# buck.net
KiCad netlist of a schematic drawn in Altium Designer
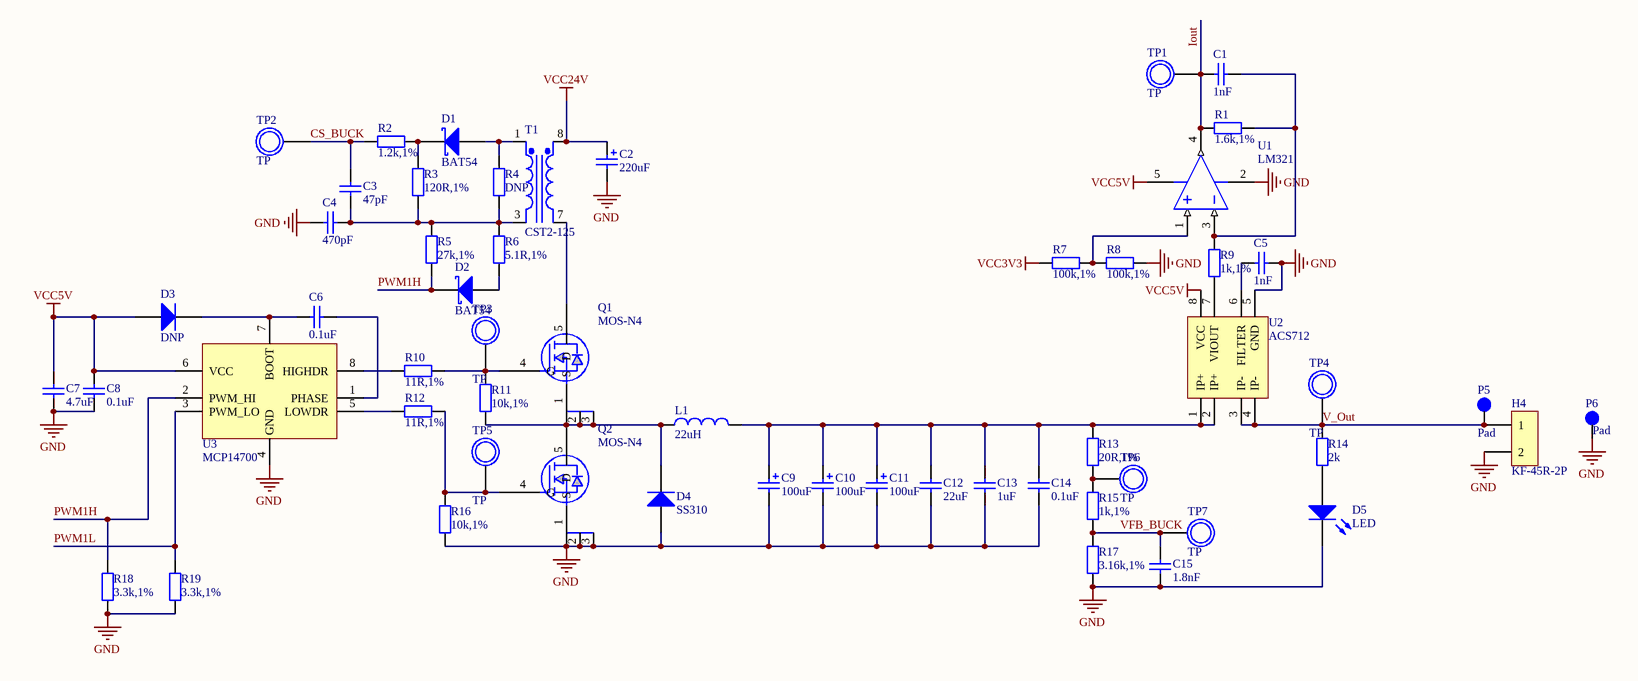
[diagram p0: buck.SchDoc]

(export (version "E")
  (design (tool "Eeschema 10.0.6"))
  (components
    (comp (ref "C1")
      (value "1nF")
      (footprint "CAP0603")
      (description "CAP NON-POL")
      (fields (field (name "TOLERANCE") "+/-10%"))
      (libsource (lib "Seer_Discrete") (part "CAP"))
    )
    (comp (ref "C2")
      (value "220uF")
      (footprint "CAPAE109103X105N")
      (description "cap pol")
      (fields (field (name "TOLERANCE") "~{+}- 10%"))
      (libsource (lib "Seer_Discrete") (part "CAP_Pol"))
    )
    (comp (ref "C3")
      (value "47pF")
      (footprint "CAP0603")
      (description "CAP NON-POL")
      (fields (field (name "TOLERANCE") "+/-10%"))
      (libsource (lib "Seer_Discrete") (part "CAP"))
    )
    (comp (ref "C4")
      (value "470pF")
      (footprint "CAP0603")
      (description "CAP NON-POL")
      (fields (field (name "TOLERANCE") "+/-10%"))
      (libsource (lib "Seer_Discrete") (part "CAP"))
    )
    (comp (ref "C5")
      (value "1nF")
      (footprint "CAP0603")
      (description "CAP NON-POL")
      (fields (field (name "TOLERANCE") "+/-10%"))
      (libsource (lib "Seer_Discrete") (part "CAP"))
    )
    (comp (ref "C6")
      (value "0.1uF")
      (footprint "CAP0603")
      (description "CAP NON-POL")
      (fields (field (name "TOLERANCE") "+/-10%"))
      (libsource (lib "Seer_Discrete") (part "CAP"))
    )
    (comp (ref "C7")
      (value "4.7uF")
      (footprint "CAP0603")
      (description "CAP NON-POL")
      (fields (field (name "TOLERANCE") "+/-10%"))
      (libsource (lib "Seer_Discrete") (part "CAP"))
    )
    (comp (ref "C8")
      (value "0.1uF")
      (footprint "CAP0603")
      (description "CAP NON-POL")
      (fields (field (name "TOLERANCE") "+/-10%"))
      (libsource (lib "Seer_Discrete") (part "CAP"))
    )
    (comp (ref "C9")
      (value "100uF")
      (footprint "CAPAE8983X105N")
      (description "cap pol")
      (fields (field (name "TOLERANCE") "~{+}- 10%"))
      (libsource (lib "Seer_Discrete") (part "CAP_Pol"))
    )
    (comp (ref "C10")
      (value "100uF")
      (footprint "CAPAE8983X105N")
      (description "cap pol")
      (fields (field (name "TOLERANCE") "~{+}- 10%"))
      (libsource (lib "Seer_Discrete") (part "CAP_Pol"))
    )
    (comp (ref "C11")
      (value "100uF")
      (footprint "CAPAE8983X105N")
      (description "cap pol")
      (fields (field (name "TOLERANCE") "~{+}- 10%"))
      (libsource (lib "Seer_Discrete") (part "CAP_Pol"))
    )
    (comp (ref "C12")
      (value "22uF")
      (footprint "CAP1206")
      (description "CAP NON-POL")
      (fields (field (name "TOLERANCE") "+/-10%"))
      (libsource (lib "Seer_Discrete") (part "CAP"))
    )
    (comp (ref "C13")
      (value "1uF")
      (footprint "CAP1206")
      (description "CAP NON-POL")
      (fields (field (name "TOLERANCE") "+/-10%"))
      (libsource (lib "Seer_Discrete") (part "CAP"))
    )
    (comp (ref "C14")
      (value "0.1uF")
      (footprint "CAP1206")
      (description "CAP NON-POL")
      (fields (field (name "TOLERANCE") "+/-10%"))
      (libsource (lib "Seer_Discrete") (part "CAP"))
    )
    (comp (ref "C15")
      (value "1.8nF")
      (footprint "CAP0603")
      (description "CAP NON-POL")
      (fields (field (name "TOLERANCE") "+/-10%"))
      (libsource (lib "Seer_Discrete") (part "CAP"))
    )
    (comp (ref "D1")
      (value "BAT54")
      (footprint "SOD250X100-2N")
      (description "Schottky Diode")
      (libsource (lib "Seer_Discrete") (part "Diode Schottky"))
    )
    (comp (ref "D2")
      (value "BAT54")
      (footprint "SOD250X100-2N")
      (description "Schottky Diode")
      (libsource (lib "Seer_Discrete") (part "Diode Schottky"))
    )
    (comp (ref "D3")
      (value "DNP")
      (footprint "SMA")
      (description "diode")
      (libsource (lib "Seer_Discrete") (part "Diode"))
    )
    (comp (ref "D4")
      (value "SS310")
      (footprint "SMA")
      (description "diode")
      (libsource (lib "Seer_Discrete") (part "Diode"))
    )
    (comp (ref "D5")
      (value "LED")
      (footprint "LED0402")
      (description "led")
      (libsource (lib "Seer_Discrete") (part "LED"))
    )
    (comp (ref "H4")
      (value "KF-45R-2P")
      (footprint "KF-45R-2P")
      (libsource (lib "Seer_XIAL") (part "KF-45R-2P"))
    )
    (comp (ref "L1")
      (value "22uH")
      (footprint "CDRH125")
      (description "Inductor")
      (libsource (lib "Seer_Discrete") (part "Inductor"))
    )
    (comp (ref "P5")
      (value "Pad")
      (footprint "PAD10x50")
      (description "PAD")
      (libsource (lib "Seer_XIAL") (part "Pad"))
    )
    (comp (ref "P6")
      (value "Pad")
      (footprint "PAD10x50")
      (description "PAD")
      (libsource (lib "Seer_XIAL") (part "Pad"))
    )
    (comp (ref "Q1")
      (value "MOS-N4")
      (footprint "QFN5x6")
      (description "N Channel MOSFET")
      (libsource (lib "Seer_Discrete") (part "MOS-N4"))
    )
    (comp (ref "Q2")
      (value "MOS-N4")
      (footprint "QFN5x6")
      (description "N Channel MOSFET")
      (libsource (lib "Seer_Discrete") (part "MOS-N4"))
    )
    (comp (ref "R1")
      (value "1.6k,1%")
      (footprint "RES0603")
      (description "res")
      (libsource (lib "") (part "RES_1"))
    )
    (comp (ref "R2")
      (value "1.2k,1%")
      (footprint "RES0603")
      (description "res")
      (libsource (lib "Seer_Discrete") (part "RES"))
    )
    (comp (ref "R3")
      (value "120R,1%")
      (footprint "RES0603")
      (description "res")
      (libsource (lib "") (part "RES_2"))
    )
    (comp (ref "R4")
      (value "DNP")
      (footprint "RES0603")
      (description "res")
      (libsource (lib "") (part "RES_3"))
    )
    (comp (ref "R5")
      (value "27k,1%")
      (footprint "RES0603")
      (description "res")
      (libsource (lib "") (part "RES_2"))
    )
    (comp (ref "R6")
      (value "5.1R,1%")
      (footprint "RES0603")
      (description "res")
      (libsource (lib "") (part "RES_2"))
    )
    (comp (ref "R7")
      (value "100k,1%")
      (footprint "RES0603")
      (description "res")
      (libsource (lib "Seer_Discrete") (part "RES"))
    )
    (comp (ref "R8")
      (value "100k,1%")
      (footprint "RES0603")
      (description "res")
      (libsource (lib "Seer_Discrete") (part "RES"))
    )
    (comp (ref "R9")
      (value "1k,1%")
      (footprint "RES0603")
      (description "res")
      (libsource (lib "") (part "RES_2"))
    )
    (comp (ref "R10")
      (value "11R,1%")
      (footprint "RES0603")
      (description "res")
      (libsource (lib "Seer_Discrete") (part "RES"))
    )
    (comp (ref "R11")
      (value "10k,1%")
      (footprint "RES0603")
      (description "res")
      (libsource (lib "") (part "RES_2"))
    )
    (comp (ref "R12")
      (value "11R,1%")
      (footprint "RES0603")
      (description "res")
      (libsource (lib "Seer_Discrete") (part "RES"))
    )
    (comp (ref "R13")
      (value "20R,1%")
      (footprint "RES0603")
      (description "res")
      (libsource (lib "") (part "RES_2"))
    )
    (comp (ref "R14")
      (value "2k")
      (footprint "RES0402")
      (description "res")
      (libsource (lib "") (part "RES_3"))
    )
    (comp (ref "R15")
      (value "1k,1%")
      (footprint "RES0603")
      (description "res")
      (libsource (lib "") (part "RES_2"))
    )
    (comp (ref "R16")
      (value "10k,1%")
      (footprint "RES0603")
      (description "res")
      (libsource (lib "") (part "RES_2"))
    )
    (comp (ref "R17")
      (value "3.16k,1%")
      (footprint "RES0603")
      (description "res")
      (libsource (lib "") (part "RES_2"))
    )
    (comp (ref "R18")
      (value "3.3k,1%")
      (footprint "RES0603")
      (description "res")
      (libsource (lib "") (part "RES_3"))
    )
    (comp (ref "R19")
      (value "3.3k,1%")
      (footprint "RES0603")
      (description "res")
      (libsource (lib "") (part "RES_3"))
    )
    (comp (ref "T1")
      (value "CST2-125")
      (footprint "CST2-125")
      (description "Current Transformer 1:125")
      (libsource (lib "Seer_IC") (part "CST2-125"))
    )
    (comp (ref "TP1")
      (value "TP")
      (footprint "PAD85R")
      (description "test point")
      (libsource (lib "Seer_XIAL") (part "Test_Point"))
    )
    (comp (ref "TP2")
      (value "TP")
      (footprint "PAD85R")
      (description "test point")
      (libsource (lib "Seer_XIAL") (part "Test_Point"))
    )
    (comp (ref "TP3")
      (value "TP")
      (footprint "PAD85R")
      (description "test point")
      (libsource (lib "Seer_XIAL") (part "Test_Point"))
    )
    (comp (ref "TP4")
      (value "TP")
      (footprint "PAD85R")
      (description "test point")
      (libsource (lib "Seer_XIAL") (part "Test_Point"))
    )
    (comp (ref "TP5")
      (value "TP")
      (footprint "PAD85R")
      (description "test point")
      (libsource (lib "Seer_XIAL") (part "Test_Point"))
    )
    (comp (ref "TP6")
      (value "TP")
      (footprint "PAD85R")
      (description "test point")
      (libsource (lib "Seer_XIAL") (part "Test_Point"))
    )
    (comp (ref "TP7")
      (value "TP")
      (footprint "PAD85R")
      (description "test point")
      (libsource (lib "Seer_XIAL") (part "Test_Point"))
    )
    (comp (ref "U1")
      (value "LM321")
      (footprint "SOT65P210X110-5N")
      (description "Low Power Single Op Amp")
      (libsource (lib "Seer_IC") (part "LM321"))
    )
    (comp (ref "U2")
      (value "ACS712")
      (footprint "SOP127P600X175-8N")
      (libsource (lib "Seer_IC") (part "ACS712"))
    )
    (comp (ref "U3")
      (value "MCP14700")
      (footprint "SOP127P600X175-8N")
      (description "Dual Input Synchronous MOSFET Driver")
      (libsource (lib "Seer_IC") (part "MCP14700"))
    )
  )
  (nets
    (net (code "1") (name "/CS_BUCK") (class "Default")
      (node (ref "C3") (pin "2") (pinfunction "2_2") (pintype "passive"))
      (node (ref "R2") (pin "2") (pinfunction "2_2") (pintype "passive"))
      (node (ref "TP2") (pin "1") (pinfunction "1_1") (pintype "passive"))
    )
    (net (code "2") (name "/Iout") (class "Default")
      (node (ref "C1") (pin "2") (pinfunction "2_2") (pintype "passive"))
      (node (ref "R1") (pin "1") (pinfunction "1_1") (pintype "passive"))
      (node (ref "TP1") (pin "1") (pinfunction "1_1") (pintype "passive"))
      (node (ref "U1") (pin "4") (pinfunction "OUT_4") (pintype "output"))
    )
    (net (code "3") (name "/PWM1H") (class "Default")
      (node (ref "D2") (pin "1") (pinfunction "K_1") (pintype "passive"))
      (node (ref "R18") (pin "2") (pinfunction "2_2") (pintype "passive"))
      (node (ref "R5") (pin "2") (pinfunction "2_2") (pintype "passive"))
      (node (ref "U3") (pin "2") (pinfunction "PWM_HI_2") (pintype "passive"))
    )
    (net (code "4") (name "/PWM1L") (class "Default")
      (node (ref "R19") (pin "2") (pinfunction "2_2") (pintype "passive"))
      (node (ref "U3") (pin "3") (pinfunction "PWM_LO_3") (pintype "passive"))
    )
    (net (code "5") (name "/VFB_BUCK") (class "Default")
      (node (ref "C15") (pin "2") (pinfunction "2_2") (pintype "passive"))
      (node (ref "R15") (pin "2") (pinfunction "2_2") (pintype "passive"))
      (node (ref "R17") (pin "1") (pinfunction "1_1") (pintype "passive"))
      (node (ref "TP7") (pin "1") (pinfunction "1_1") (pintype "passive"))
    )
    (net (code "6") (name "/V_Out") (class "Default")
      (node (ref "H4") (pin "1") (pinfunction "1_1") (pintype "passive"))
      (node (ref "P5") (pin "1") (pinfunction "1_1") (pintype "passive"))
      (node (ref "R14") (pin "2") (pinfunction "2_2") (pintype "passive"))
      (node (ref "TP4") (pin "1") (pinfunction "1_1") (pintype "passive"))
      (node (ref "U2") (pin "3") (pinfunction "IP-_3") (pintype "passive"))
      (node (ref "U2") (pin "4") (pinfunction "IP-_4") (pintype "passive"))
    )
    (net (code "7") (name "GND") (class "Default")
      (node (ref "C10") (pin "1") (pinfunction "1_1") (pintype "passive"))
      (node (ref "C11") (pin "1") (pinfunction "1_1") (pintype "passive"))
      (node (ref "C12") (pin "1") (pinfunction "1_1") (pintype "passive"))
      (node (ref "C13") (pin "1") (pinfunction "1_1") (pintype "passive"))
      (node (ref "C14") (pin "1") (pinfunction "1_1") (pintype "passive"))
      (node (ref "C15") (pin "1") (pinfunction "1_1") (pintype "passive"))
      (node (ref "C2") (pin "1") (pinfunction "1_1") (pintype "passive"))
      (node (ref "C4") (pin "2") (pinfunction "2_2") (pintype "passive"))
      (node (ref "C5") (pin "1") (pinfunction "1_1") (pintype "passive"))
      (node (ref "C7") (pin "1") (pinfunction "1_1") (pintype "passive"))
      (node (ref "C8") (pin "1") (pinfunction "1_1") (pintype "passive"))
      (node (ref "C9") (pin "1") (pinfunction "1_1") (pintype "passive"))
      (node (ref "D4") (pin "1") (pinfunction "A_1") (pintype "passive"))
      (node (ref "D5") (pin "2") (pinfunction "K_2") (pintype "passive"))
      (node (ref "H4") (pin "2") (pinfunction "2_2") (pintype "passive"))
      (node (ref "P6") (pin "1") (pinfunction "1_1") (pintype "passive"))
      (node (ref "Q2") (pin "1") (pinfunction "S_1") (pintype "passive"))
      (node (ref "Q2") (pin "2") (pintype "passive"))
      (node (ref "Q2") (pin "3") (pintype "passive"))
      (node (ref "R16") (pin "2") (pinfunction "2_2") (pintype "passive"))
      (node (ref "R17") (pin "2") (pinfunction "2_2") (pintype "passive"))
      (node (ref "R18") (pin "1") (pinfunction "1_1") (pintype "passive"))
      (node (ref "R19") (pin "1") (pinfunction "1_1") (pintype "passive"))
      (node (ref "R8") (pin "1") (pinfunction "1_1") (pintype "passive"))
      (node (ref "U1") (pin "2") (pinfunction "V-_2") (pintype "power_in"))
      (node (ref "U2") (pin "5") (pinfunction "GND_5") (pintype "passive"))
      (node (ref "U3") (pin "4") (pinfunction "GND_4") (pintype "passive"))
    )
    (net (code "8") (name "Net-(C10-Pad2)") (class "Default")
      (node (ref "C10") (pin "2") (pinfunction "2_2") (pintype "passive"))
      (node (ref "C11") (pin "2") (pinfunction "2_2") (pintype "passive"))
      (node (ref "C12") (pin "2") (pinfunction "2_2") (pintype "passive"))
      (node (ref "C13") (pin "2") (pinfunction "2_2") (pintype "passive"))
      (node (ref "C14") (pin "2") (pinfunction "2_2") (pintype "passive"))
      (node (ref "C9") (pin "2") (pinfunction "2_2") (pintype "passive"))
      (node (ref "L1") (pin "2") (pinfunction "2_2") (pintype "passive"))
      (node (ref "R13") (pin "1") (pinfunction "1_1") (pintype "passive"))
      (node (ref "U2") (pin "1") (pinfunction "IP+_1") (pintype "passive"))
      (node (ref "U2") (pin "2") (pinfunction "IP+_2") (pintype "passive"))
    )
    (net (code "9") (name "Net-(D1-A)") (class "Default")
      (node (ref "D1") (pin "2") (pinfunction "A_2") (pintype "passive"))
      (node (ref "R4") (pin "2") (pinfunction "2_2") (pintype "passive"))
      (node (ref "T1") (pin "1") (pinfunction "Sec+_1") (pintype "passive"))
    )
    (net (code "10") (name "Net-(D1-K)") (class "Default")
      (node (ref "D1") (pin "1") (pinfunction "K_1") (pintype "passive"))
      (node (ref "R2") (pin "1") (pinfunction "1_1") (pintype "passive"))
      (node (ref "R3") (pin "1") (pinfunction "1_1") (pintype "passive"))
    )
    (net (code "11") (name "Net-(D2-A)") (class "Default")
      (node (ref "D2") (pin "2") (pinfunction "A_2") (pintype "passive"))
      (node (ref "R6") (pin "2") (pinfunction "2_2") (pintype "passive"))
    )
    (net (code "12") (name "Net-(D3-K)") (class "Default")
      (node (ref "C6") (pin "2") (pinfunction "2_2") (pintype "passive"))
      (node (ref "D3") (pin "2") (pinfunction "K_2") (pintype "passive"))
      (node (ref "U3") (pin "7") (pinfunction "BOOT_7") (pintype "passive"))
    )
    (net (code "13") (name "Net-(D4-K)") (class "Default")
      (node (ref "D4") (pin "2") (pinfunction "K_2") (pintype "passive"))
      (node (ref "L1") (pin "1") (pinfunction "1_1") (pintype "passive"))
      (node (ref "Q1") (pin "1") (pinfunction "S_1") (pintype "passive"))
      (node (ref "Q1") (pin "2") (pintype "passive"))
      (node (ref "Q1") (pin "3") (pintype "passive"))
      (node (ref "Q2") (pin "5") (pinfunction "D_5") (pintype "passive"))
      (node (ref "R11") (pin "2") (pinfunction "2_2") (pintype "passive"))
    )
    (net (code "14") (name "Net-(D5-A)") (class "Default")
      (node (ref "D5") (pin "1") (pinfunction "A_1") (pintype "passive"))
      (node (ref "R14") (pin "1") (pinfunction "1_1") (pintype "passive"))
    )
    (net (code "15") (name "Net-(Q1-D)") (class "Default")
      (node (ref "Q1") (pin "5") (pinfunction "D_5") (pintype "passive"))
      (node (ref "T1") (pin "7") (pinfunction "Pri-_7") (pintype "passive"))
    )
    (net (code "16") (name "Net-(Q1-G)") (class "Default")
      (node (ref "Q1") (pin "4") (pinfunction "G_4") (pintype "passive"))
      (node (ref "R10") (pin "1") (pinfunction "1_1") (pintype "passive"))
      (node (ref "R11") (pin "1") (pinfunction "1_1") (pintype "passive"))
      (node (ref "TP3") (pin "1") (pinfunction "1_1") (pintype "passive"))
    )
    (net (code "17") (name "Net-(Q2-G)") (class "Default")
      (node (ref "Q2") (pin "4") (pinfunction "G_4") (pintype "passive"))
      (node (ref "R12") (pin "1") (pinfunction "1_1") (pintype "passive"))
      (node (ref "R16") (pin "1") (pinfunction "1_1") (pintype "passive"))
      (node (ref "TP5") (pin "1") (pinfunction "1_1") (pintype "passive"))
    )
    (net (code "18") (name "Net-(R13-Pad2)") (class "Default")
      (node (ref "R13") (pin "2") (pinfunction "2_2") (pintype "passive"))
      (node (ref "R15") (pin "1") (pinfunction "1_1") (pintype "passive"))
      (node (ref "TP6") (pin "1") (pinfunction "1_1") (pintype "passive"))
    )
    (net (code "19") (name "Net-(T1-Sec-)") (class "Default")
      (node (ref "C3") (pin "1") (pinfunction "1_1") (pintype "passive"))
      (node (ref "C4") (pin "1") (pinfunction "1_1") (pintype "passive"))
      (node (ref "R3") (pin "2") (pinfunction "2_2") (pintype "passive"))
      (node (ref "R4") (pin "1") (pinfunction "1_1") (pintype "passive"))
      (node (ref "R5") (pin "1") (pinfunction "1_1") (pintype "passive"))
      (node (ref "R6") (pin "1") (pinfunction "1_1") (pintype "passive"))
      (node (ref "T1") (pin "3") (pinfunction "Sec-_3") (pintype "passive"))
    )
    (net (code "20") (name "Net-(U1-IN+)") (class "Default")
      (node (ref "R7") (pin "1") (pinfunction "1_1") (pintype "passive"))
      (node (ref "R8") (pin "2") (pinfunction "2_2") (pintype "passive"))
      (node (ref "U1") (pin "1") (pinfunction "IN+_1") (pintype "input"))
    )
    (net (code "21") (name "Net-(U1-IN-)") (class "Default")
      (node (ref "C1") (pin "1") (pinfunction "1_1") (pintype "passive"))
      (node (ref "R1") (pin "2") (pinfunction "2_2") (pintype "passive"))
      (node (ref "R9") (pin "1") (pinfunction "1_1") (pintype "passive"))
      (node (ref "U1") (pin "3") (pinfunction "IN-_3") (pintype "input"))
    )
    (net (code "22") (name "Net-(U2-FILTER)") (class "Default")
      (node (ref "C5") (pin "2") (pinfunction "2_2") (pintype "passive"))
      (node (ref "U2") (pin "6") (pinfunction "FILTER_6") (pintype "passive"))
    )
    (net (code "23") (name "Net-(U2-VIOUT)") (class "Default")
      (node (ref "R9") (pin "2") (pinfunction "2_2") (pintype "passive"))
      (node (ref "U2") (pin "7") (pinfunction "VIOUT_7") (pintype "passive"))
    )
    (net (code "24") (name "Net-(U3-HIGHDR)") (class "Default")
      (node (ref "R10") (pin "2") (pinfunction "2_2") (pintype "passive"))
      (node (ref "U3") (pin "8") (pinfunction "HIGHDR_8") (pintype "passive"))
    )
    (net (code "25") (name "Net-(U3-LOWDR)") (class "Default")
      (node (ref "R12") (pin "2") (pinfunction "2_2") (pintype "passive"))
      (node (ref "U3") (pin "5") (pinfunction "LOWDR_5") (pintype "passive"))
    )
    (net (code "26") (name "Net-(U3-PHASE)") (class "Default")
      (node (ref "C6") (pin "1") (pinfunction "1_1") (pintype "passive"))
      (node (ref "U3") (pin "1") (pinfunction "PHASE_1") (pintype "passive"))
    )
    (net (code "27") (name "VCC3V3") (class "Default")
      (node (ref "R7") (pin "2") (pinfunction "2_2") (pintype "passive"))
    )
    (net (code "28") (name "VCC5V") (class "Default")
      (node (ref "C7") (pin "2") (pinfunction "2_2") (pintype "passive"))
      (node (ref "C8") (pin "2") (pinfunction "2_2") (pintype "passive"))
      (node (ref "D3") (pin "1") (pinfunction "A_1") (pintype "passive"))
      (node (ref "U1") (pin "5") (pinfunction "V+_5") (pintype "power_in"))
      (node (ref "U2") (pin "8") (pinfunction "VCC_8") (pintype "passive"))
      (node (ref "U3") (pin "6") (pinfunction "VCC_6") (pintype "passive"))
    )
    (net (code "29") (name "VCC24V") (class "Default")
      (node (ref "C2") (pin "2") (pinfunction "2_2") (pintype "passive"))
      (node (ref "T1") (pin "8") (pinfunction "Pri+_8") (pintype "passive"))
    )
  )
)
